# Power.net
KiCad netlist of a schematic drawn in Altium Designer
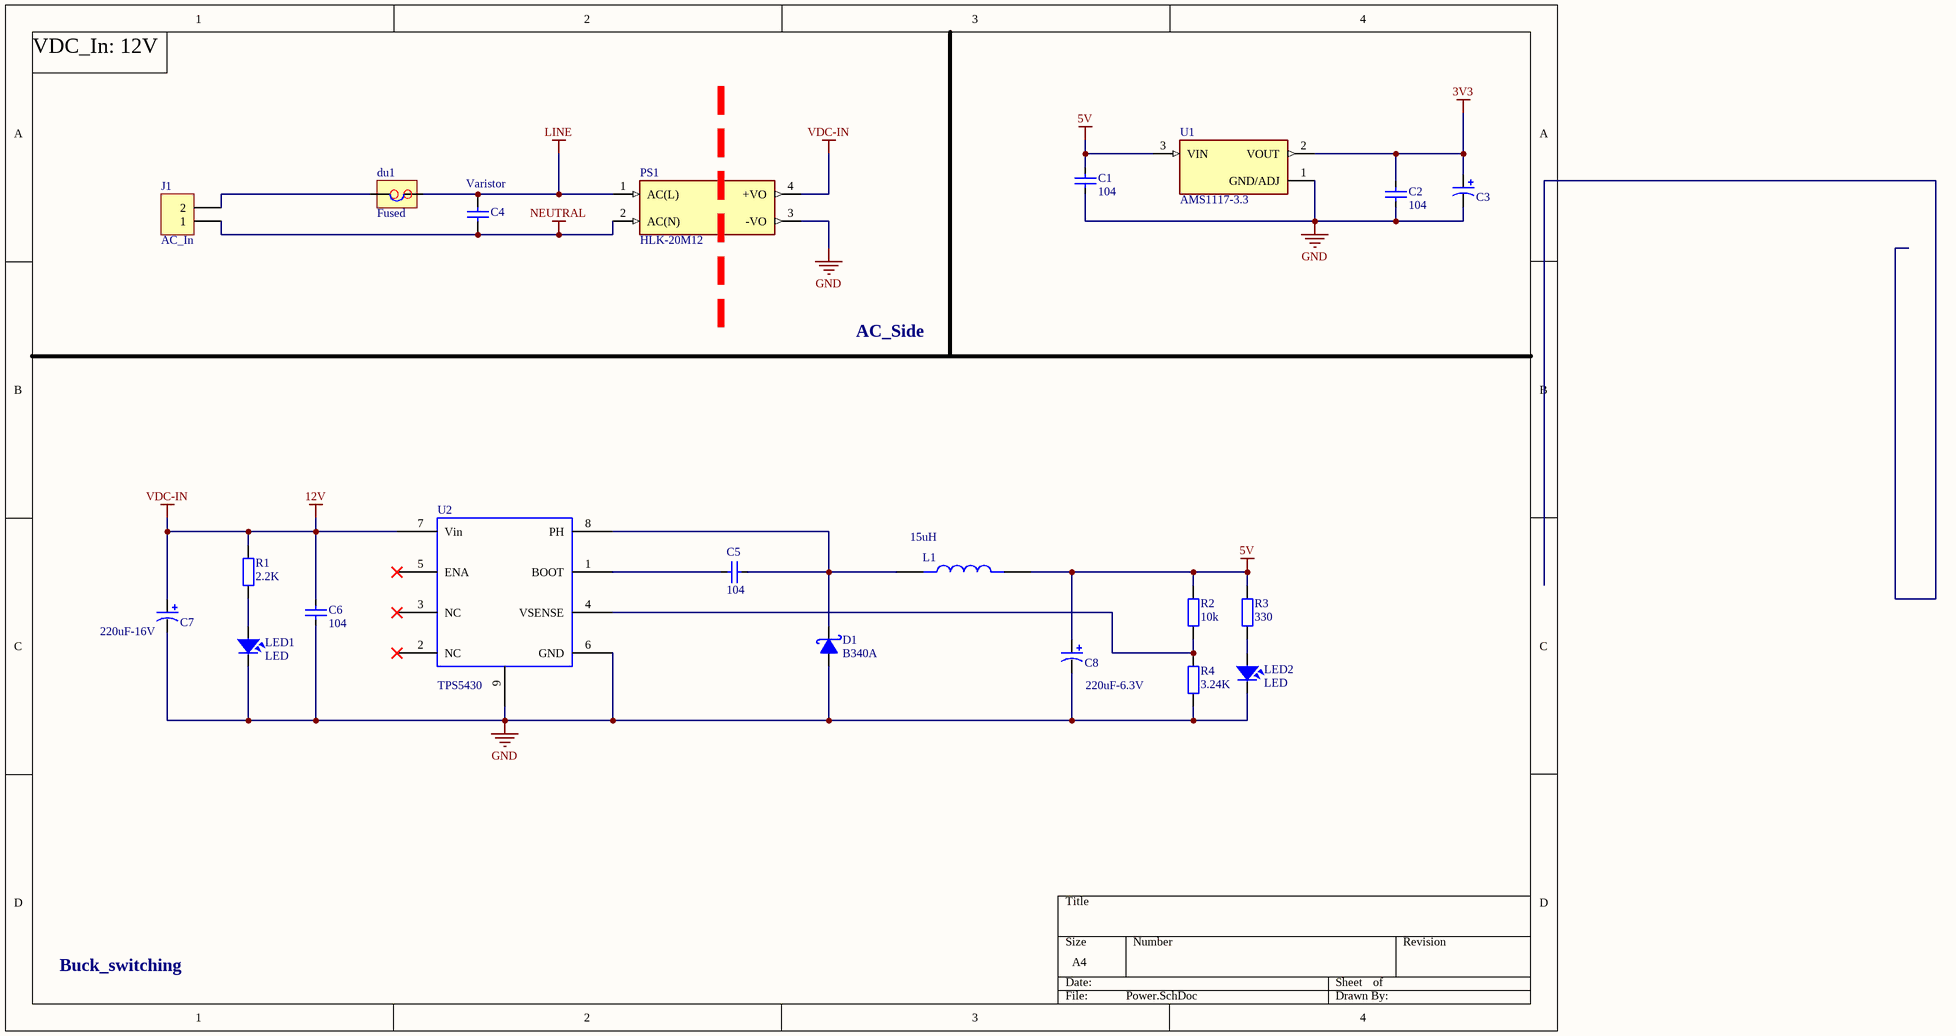
[diagram p0: Power.SchDoc]

(export (version "E")
  (design (tool "Eeschema 10.0.6"))
  (components
    (comp (ref "C1")
      (value "104")
      (footprint "CAP_0805")
      (description "Capacitor")
      (fields (field (name "PUBLISHER") "Altium Limited"))
      (libsource (lib "Main") (part "CapSMD"))
    )
    (comp (ref "C2")
      (value "104")
      (footprint "CAP_0805")
      (description "Capacitor")
      (fields (field (name "PUBLISHER") "Altium Limited"))
      (libsource (lib "Main") (part "CapSMD"))
    )
    (comp (ref "C3")
      (value "100uF")
      (footprint "CAP_7343")
      (description "https://linhkien.cxt.vn/8805-tu-tantalum-100uf-63v-7343-73x43mm.html")
      (libsource (lib "Main") (part "CAP_TAN_SMD"))
    )
    (comp (ref "C4")
      (value "Varistor")
      (footprint "CAP_MICA_6MM")
      (description "10D561K")
      (fields (field (name "PUBLISHER") "Altium Limited"))
      (libsource (lib "Main") (part "CapCeramic"))
    )
    (comp (ref "C5")
      (value "104")
      (footprint "CAP_0805")
      (description "https://linhkien.cxt.vn/9232-tu-104-01uf-100nf-0805-25v-10-10c.html")
      (fields (field (name "PUBLISHER") "Altium Limited"))
      (libsource (lib "My Library") (part "CapSMD"))
    )
    (comp (ref "C6")
      (value "104")
      (footprint "CAP_0805")
      (description "https://linhkien.cxt.vn/9232-tu-104-01uf-100nf-0805-25v-10-10c.html")
      (fields (field (name "PUBLISHER") "Altium Limited"))
      (libsource (lib "My Library") (part "CapSMD"))
    )
    (comp (ref "C7")
      (value "220uF-16V")
      (footprint "CAP_7343")
      (description "https://linhkien.cxt.vn/2032-tu-tantalum-7343-cac-gia-tri.html")
      (libsource (lib "My Library") (part "CAP_TAN_SMD"))
    )
    (comp (ref "C8")
      (value "220uF-6.3V")
      (footprint "CAP_7343")
      (description "https://linhkien.cxt.vn/2032-tu-tantalum-7343-cac-gia-tri.html")
      (libsource (lib "My Library") (part "CAP_TAN_SMD"))
    )
    (comp (ref "D1")
      (value "B340A")
      (footprint "SMA")
      (description "https://linhkien.cxt.vn/4563-b340a-13-f-diode-schottky-3a-40v-smado-214ac.html")
      (libsource (lib "My Library") (part "Diode Schottky"))
    )
    (comp (ref "du1")
      (value "Fused")
      (footprint "FUSRR1015W52L1650T300H2620")
      (libsource (lib "Main") (part "FuseNote2"))
    )
    (comp (ref "J1")
      (value "AC_In")
      (footprint "KF2-5.08T")
      (fields
        (field (name "MANUFACTURER") "Würth Elektronik eiSos GmbH")
        (field (name "PARTNO") "691103110002")
        (field (name "CREATED BY") "Karrer Zheng")
      )
      (libsource (lib "Main") (part "KF2"))
    )
    (comp (ref "L1")
      (value "15uH")
      (footprint "IND_ASPI-0630LR-150M-T15")
      (description "https://linhkien.cxt.vn/3445-cuon-cam-150-15uh-0630-3a-7x7x3mm.html")
      (fields
        (field (name "MF") "Abracon LLC")
        (field (name "DIGI-KEY_PART_NUMBER") "ASPI-0630LR-150M-T15TR-ND")
      )
      (libsource (lib "ASPI-0630LR-150M-T15") (part "ASPI-0630LR-150M-T15"))
    )
    (comp (ref "LED1")
      (value "LED")
      (footprint "LED-0805-Blue")
      (description "LED Single colour Green and Red")
      (libsource (lib "Main") (part "LED"))
    )
    (comp (ref "LED2")
      (value "LED")
      (footprint "LED-0805-Blue")
      (description "LED Single colour Green and Red")
      (libsource (lib "Main") (part "LED"))
    )
    (comp (ref "PS1")
      (value "HLK-20M12")
      (footprint "CONV_HLK-20M12")
      (description "20W ultra-small series module power supply")
      (fields (field (name "MF") "Hi-link"))
      (libsource (lib "HLK-20M12") (part "HLK-20M12"))
    )
    (comp (ref "R1")
      (value "2.2K")
      (footprint "RES-SMD-0805")
      (description "https://linhkien.cxt.vn/5089-dien-tro-0805-1-thong-so-tu-1k-den-91k.html")
      (fields
        (field (name "MANUFACTURER") "Generic Components")
        (field (name "PUBLISHER") "Altium Hobart Technology Centre")
      )
      (libsource (lib "Main") (part "Resistor - SMD"))
    )
    (comp (ref "R2")
      (value "10k")
      (footprint "RES-SMD-0805")
      (description "https://linhkien.cxt.vn/6741-dien-tro-0805-1-thong-so-tu-1k-den-91k.html")
      (fields
        (field (name "MANUFACTURER") "Generic Components")
        (field (name "PUBLISHER") "Altium Hobart Technology Centre")
      )
      (libsource (lib "My Library") (part "Resistor - SMD"))
    )
    (comp (ref "R3")
      (value "330")
      (footprint "RES-SMD-0805")
      (description "https://linhkien.cxt.vn/2346-dien-tro-0805-1-thong-so-tu-1k-den-91k.html")
      (fields
        (field (name "MANUFACTURER") "Generic Components")
        (field (name "PUBLISHER") "Altium Hobart Technology Centre")
      )
      (libsource (lib "Main") (part "Resistor - SMD"))
    )
    (comp (ref "R4")
      (value "3.24K")
      (footprint "RES-SMD-0805")
      (description "https://linhkien.cxt.vn/6162-dien-tro-59k-0805-1-50c.html")
      (fields
        (field (name "MANUFACTURER") "Generic Components")
        (field (name "PUBLISHER") "Altium Hobart Technology Centre")
      )
      (libsource (lib "My Library") (part "Resistor - SMD"))
    )
    (comp (ref "U1")
      (value "AMS1117-3.3")
      (footprint "SOT229P700X180-4N")
      (description "Sot223/Pkg 1-Amp 3.3-Volt Low Drop Out Voltage Regulatator")
      (fields (field (name "MF") "Advanced Monolithic Systems"))
      (libsource (lib "AMS1117-3.3") (part "AMS1117-3.3"))
    )
    (comp (ref "U2")
      (value "TPS5430")
      (footprint "TPS5430-2")
      (description "https://linhkien.cxt.vn/7312-tps54302ddct-ic-reg-buck-adj-3a-tsot23-6.html")
      (fields (field (name "NAME") "TPS5430"))
      (libsource (lib "My Library") (part "TPS5430"))
    )
  )
  (nets
    (net (code "1") (name "3V3") (class "Default")
      (node (ref "C2") (pin "1") (pinfunction "1_1") (pintype "passive"))
      (node (ref "C3") (pin "1") (pinfunction "1_1") (pintype "passive"))
      (node (ref "U1") (pin "2") (pinfunction "VOUT_2") (pintype "output"))
    )
    (net (code "2") (name "5V") (class "Default")
      (node (ref "C1") (pin "1") (pinfunction "1_1") (pintype "passive"))
      (node (ref "C8") (pin "1") (pinfunction "1_1") (pintype "passive"))
      (node (ref "L1") (pin "2") (pinfunction "2_2") (pintype "passive"))
      (node (ref "R2") (pin "2") (pinfunction "2_2") (pintype "passive"))
      (node (ref "R3") (pin "2") (pinfunction "2_2") (pintype "passive"))
      (node (ref "U1") (pin "3") (pinfunction "VIN_3") (pintype "input"))
    )
    (net (code "3") (name "12V") (class "Default")
      (node (ref "C6") (pin "1") (pinfunction "1_1") (pintype "passive"))
      (node (ref "C7") (pin "1") (pinfunction "1_1") (pintype "passive"))
      (node (ref "PS1") (pin "4") (pinfunction "+VO_4") (pintype "output"))
      (node (ref "R1") (pin "2") (pinfunction "2_2") (pintype "passive"))
      (node (ref "U2") (pin "7") (pinfunction "Vin_7") (pintype "passive"))
    )
    (net (code "4") (name "GND") (class "Default")
      (node (ref "C1") (pin "2") (pinfunction "2_2") (pintype "passive"))
      (node (ref "C2") (pin "2") (pinfunction "2_2") (pintype "passive"))
      (node (ref "C3") (pin "2") (pinfunction "2_2") (pintype "passive"))
      (node (ref "C6") (pin "2") (pinfunction "2_2") (pintype "passive"))
      (node (ref "C7") (pin "2") (pinfunction "2_2") (pintype "passive"))
      (node (ref "C8") (pin "2") (pinfunction "2_2") (pintype "passive"))
      (node (ref "D1") (pin "1") (pinfunction "A_1") (pintype "passive"))
      (node (ref "LED1") (pin "2") (pinfunction "2_2") (pintype "passive"))
      (node (ref "LED2") (pin "2") (pinfunction "2_2") (pintype "passive"))
      (node (ref "PS1") (pin "3") (pinfunction "-VO_3") (pintype "output"))
      (node (ref "R4") (pin "1") (pinfunction "1_1") (pintype "passive"))
      (node (ref "U1") (pin "1") (pinfunction "GND/ADJ_1") (pintype "power_in"))
      (node (ref "U2") (pin "6") (pinfunction "GND_6") (pintype "passive"))
      (node (ref "U2") (pin "9") (pinfunction "PWR_PAD_9") (pintype "passive"))
    )
    (net (code "5") (name "LINE") (class "Default")
      (node (ref "C4") (pin "1") (pinfunction "1_1") (pintype "passive"))
      (node (ref "PS1") (pin "1") (pinfunction "AC(L)_1") (pintype "input"))
      (node (ref "du1") (pin "2") (pinfunction "2_2") (pintype "passive"))
    )
    (net (code "6") (name "NEUTRAL") (class "Default")
      (node (ref "C4") (pin "2") (pinfunction "2_2") (pintype "passive"))
      (node (ref "J1") (pin "1") (pinfunction "1_1") (pintype "passive"))
      (node (ref "PS1") (pin "2") (pinfunction "AC(N)_2") (pintype "input"))
    )
    (net (code "7") (name "Net-(D1-K)") (class "Default")
      (node (ref "C5") (pin "2") (pinfunction "2_2") (pintype "passive"))
      (node (ref "D1") (pin "2") (pinfunction "K_2") (pintype "passive"))
      (node (ref "L1") (pin "1") (pinfunction "1_1") (pintype "passive"))
      (node (ref "U2") (pin "8") (pinfunction "PH_8") (pintype "passive"))
    )
    (net (code "8") (name "Net-(J1-Pad2)") (class "Default")
      (node (ref "J1") (pin "2") (pinfunction "2_2") (pintype "passive"))
      (node (ref "du1") (pin "1") (pinfunction "1_1") (pintype "passive"))
    )
    (net (code "9") (name "Net-(LED1-Pad1)") (class "Default")
      (node (ref "LED1") (pin "1") (pinfunction "1_1") (pintype "passive"))
      (node (ref "R1") (pin "1") (pinfunction "1_1") (pintype "passive"))
    )
    (net (code "10") (name "Net-(LED2-Pad1)") (class "Default")
      (node (ref "LED2") (pin "1") (pinfunction "1_1") (pintype "passive"))
      (node (ref "R3") (pin "1") (pinfunction "1_1") (pintype "passive"))
    )
    (net (code "11") (name "Net-(U2-BOOT)") (class "Default")
      (node (ref "C5") (pin "1") (pinfunction "1_1") (pintype "passive"))
      (node (ref "U2") (pin "1") (pinfunction "BOOT_1") (pintype "passive"))
    )
    (net (code "12") (name "Net-(U2-VSENSE)") (class "Default")
      (node (ref "R2") (pin "1") (pinfunction "1_1") (pintype "passive"))
      (node (ref "R4") (pin "2") (pinfunction "2_2") (pintype "passive"))
      (node (ref "U2") (pin "4") (pinfunction "VSENSE_4") (pintype "passive"))
    )
    (net (code "13") (name "unconnected-(U2-ENA-Pad5)") (class "Default")
      (node (ref "U2") (pin "5") (pinfunction "ENA_5") (pintype "passive+no_connect"))
    )
    (net (code "14") (name "unconnected-(U2-NC-Pad2)") (class "Default")
      (node (ref "U2") (pin "2") (pinfunction "NC_2") (pintype "passive+no_connect"))
    )
    (net (code "15") (name "unconnected-(U2-NC-Pad3)") (class "Default")
      (node (ref "U2") (pin "3") (pinfunction "NC_3") (pintype "passive+no_connect"))
    )
  )
)
